# V1_0.net
KiCad netlist of a schematic drawn in Altium Designer
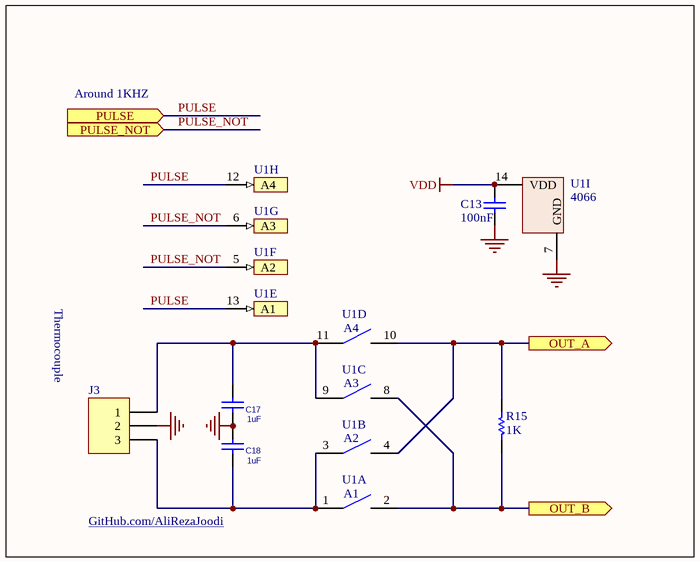
[diagram p0: V1.0.SchDoc]

(export (version "E")
  (design (tool "Eeschema 10.0.6"))
  (components
    (comp (ref "C13")
      (value "100nF")
      (footprint "CAPNTO2.54-3.05x1.78A")
      (description "Capacitor")
      (fields (field (name "MANUFACTURER") "Generic Components") (field (name "PUBLISHER") "Altium Limited"))
      (libsource (lib "Miscellaneous Devices") (part "Cap"))
    )
    (comp (ref "C17")
      (value "1uF")
      (footprint "C_SMD_CER_0805")
      (description "Capacitor, Ceramic Multilayer")
      (libsource (lib "Passive") (part "Capacitor_Ceramic"))
    )
    (comp (ref "C18")
      (value "1uF")
      (footprint "C_SMD_CER_0805")
      (description "Capacitor, Ceramic Multilayer")
      (libsource (lib "Passive") (part "Capacitor_Ceramic"))
    )
    (comp (ref "J3")
      (value "3PIN")
      (footprint "Fonics_3PIN_1")
      (description "Header, 3-Pin")
      (fields (field (name "MANUFACTURER") "Generic Components") (field (name "PUBLISHER") "Altium Limited"))
      (libsource (lib "Miscellaneous Connectors") (part "Header 3"))
    )
    (comp (ref "R15")
      (value "1K")
      (footprint "AXIAL-0.4")
      (description "Resistor")
      (fields (field (name "PUBLISHER") "Altium Limited"))
      (libsource (lib "Miscellaneous Devices") (part "Res1"))
    )
    (comp (ref "U1")
      (value "4066")
      (footprint "DIP14")
      (description "Switch")
      (libsource (lib "my Libraries") (part "CD4066"))
    )
  )
  (nets
    (net (code "1") (name "/OUT_A") (class "Default")
      (node (ref "R15") (pin "2") (pinfunction "2_2") (pintype "passive"))
      (node (ref "U1") (pin "10") (pinfunction "Y4_10") (pintype "passive"))
      (node (ref "U1") (pin "4") (pinfunction "Y2_4") (pintype "passive"))
    )
    (net (code "2") (name "/OUT_B") (class "Default")
      (node (ref "R15") (pin "1") (pinfunction "1_1") (pintype "passive"))
      (node (ref "U1") (pin "2") (pinfunction "Y1_2") (pintype "passive"))
      (node (ref "U1") (pin "8") (pinfunction "Y3_8") (pintype "passive"))
    )
    (net (code "3") (name "/PULSE") (class "Default")
      (node (ref "U1") (pin "12") (pinfunction "A4_12") (pintype "input"))
      (node (ref "U1") (pin "13") (pinfunction "A1_13") (pintype "input"))
    )
    (net (code "4") (name "/PULSE_NOT") (class "Default")
      (node (ref "U1") (pin "5") (pinfunction "A2_5") (pintype "input"))
      (node (ref "U1") (pin "6") (pinfunction "A3_6") (pintype "input"))
    )
    (net (code "5") (name "GND") (class "Default")
      (node (ref "C13") (pin "1") (pinfunction "1_1") (pintype "passive"))
      (node (ref "C17") (pin "2") (pinfunction "2_2") (pintype "passive"))
      (node (ref "C18") (pin "1") (pinfunction "1_1") (pintype "passive"))
      (node (ref "J3") (pin "2") (pinfunction "2_2") (pintype "passive"))
      (node (ref "U1") (pin "7") (pinfunction "GND_7") (pintype "power_in"))
    )
    (net (code "6") (name "Net-(U1A-X1)") (class "Default")
      (node (ref "C18") (pin "2") (pinfunction "2_2") (pintype "passive"))
      (node (ref "J3") (pin "3") (pinfunction "3_3") (pintype "passive"))
      (node (ref "U1") (pin "1") (pinfunction "X1_1") (pintype "passive"))
      (node (ref "U1") (pin "3") (pinfunction "X2_3") (pintype "passive"))
    )
    (net (code "7") (name "Net-(U1C-X3)") (class "Default")
      (node (ref "C17") (pin "1") (pinfunction "1_1") (pintype "passive"))
      (node (ref "J3") (pin "1") (pinfunction "1_1") (pintype "passive"))
      (node (ref "U1") (pin "11") (pinfunction "X4_11") (pintype "passive"))
      (node (ref "U1") (pin "9") (pinfunction "X3_9") (pintype "passive"))
    )
    (net (code "8") (name "VDD") (class "Default")
      (node (ref "C13") (pin "2") (pinfunction "2_2") (pintype "passive"))
      (node (ref "U1") (pin "14") (pinfunction "VDD_14") (pintype "passive"))
    )
  )
)
